# coproDeadEnd.net
KiCad netlist of a schematic drawn in EAGLE
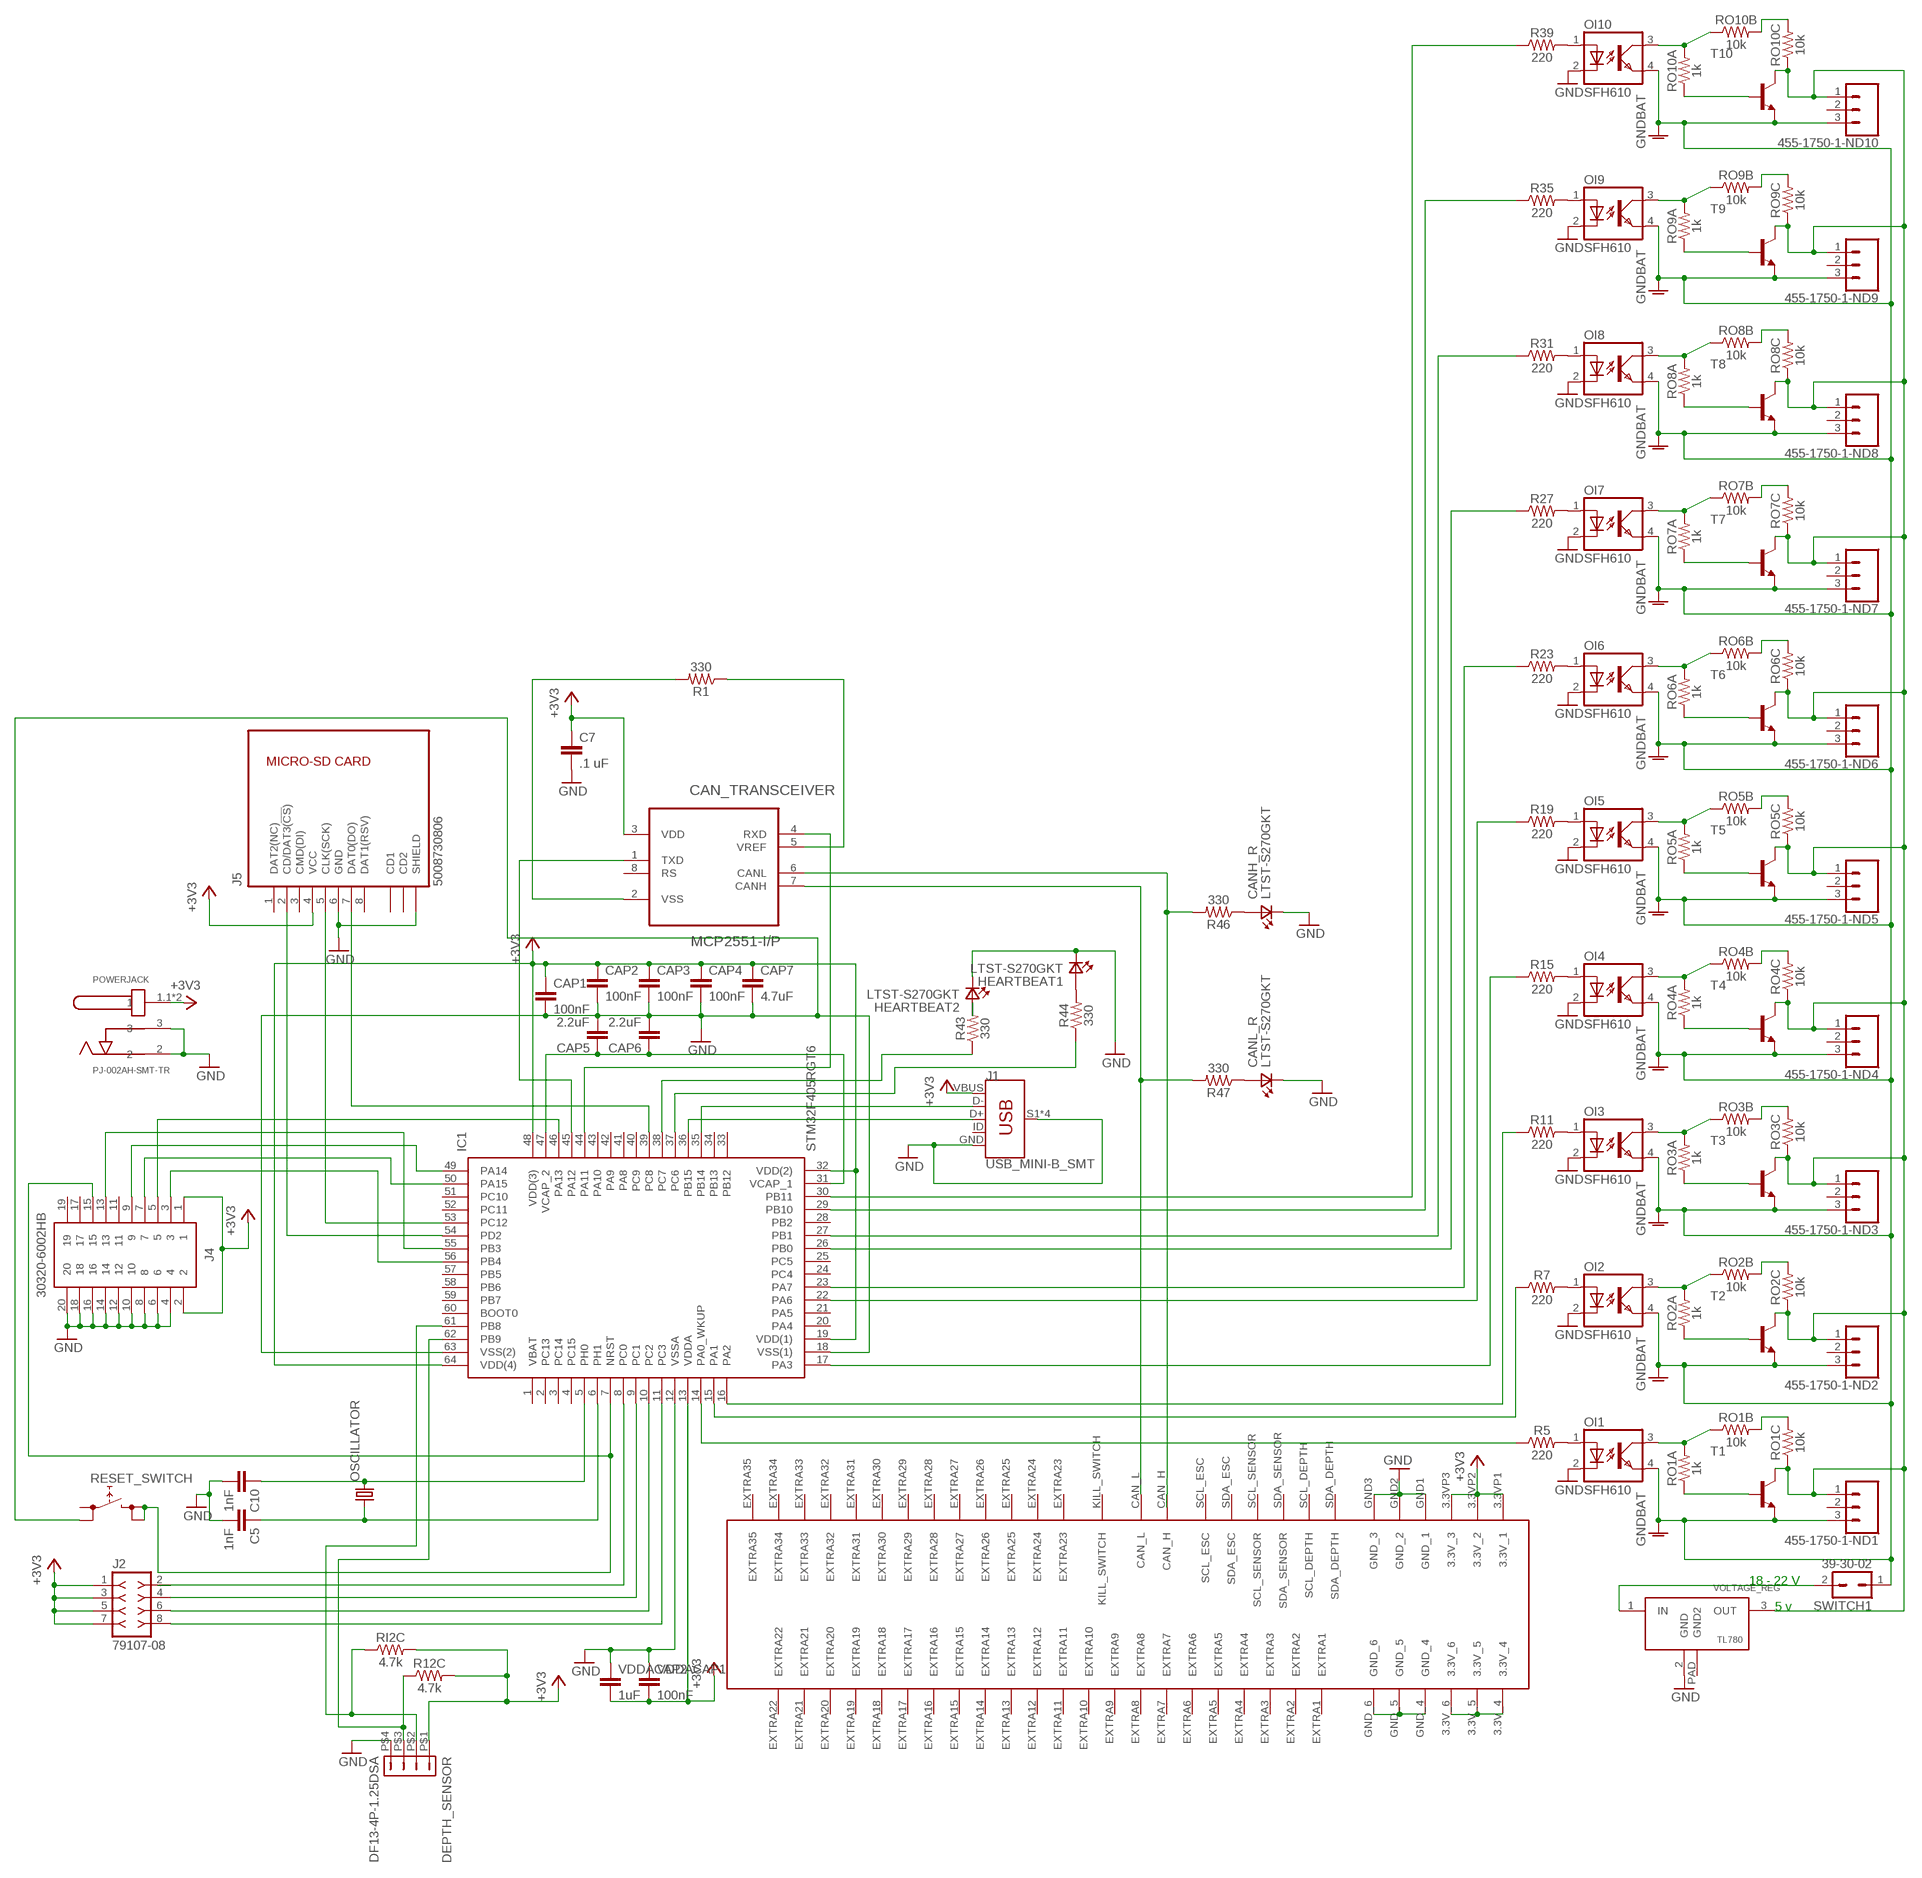
[diagram p0: schematic, sheet 1]

(export (version "E")
  (design (tool "Eeschema 10.0.6"))
  (components
    (comp (ref "455-1750-1-ND1")
      (value "CONN_03")
      (footprint "eagle-import:1X03")
      (libsource (lib "eagle-import") (part "CONN_03"))
    )
    (comp (ref "455-1750-1-ND2")
      (value "CONN_03")
      (footprint "eagle-import:1X03")
      (libsource (lib "eagle-import") (part "CONN_03"))
    )
    (comp (ref "455-1750-1-ND3")
      (value "CONN_03")
      (footprint "eagle-import:1X03")
      (libsource (lib "eagle-import") (part "CONN_03"))
    )
    (comp (ref "455-1750-1-ND4")
      (value "CONN_03")
      (footprint "eagle-import:1X03")
      (libsource (lib "eagle-import") (part "CONN_03"))
    )
    (comp (ref "455-1750-1-ND5")
      (value "CONN_03")
      (footprint "eagle-import:1X03")
      (libsource (lib "eagle-import") (part "CONN_03"))
    )
    (comp (ref "455-1750-1-ND6")
      (value "CONN_03")
      (footprint "eagle-import:1X03")
      (libsource (lib "eagle-import") (part "CONN_03"))
    )
    (comp (ref "455-1750-1-ND7")
      (value "CONN_03")
      (footprint "eagle-import:1X03")
      (libsource (lib "eagle-import") (part "CONN_03"))
    )
    (comp (ref "455-1750-1-ND8")
      (value "CONN_03")
      (footprint "eagle-import:1X03")
      (libsource (lib "eagle-import") (part "CONN_03"))
    )
    (comp (ref "455-1750-1-ND9")
      (value "CONN_03")
      (footprint "eagle-import:1X03")
      (libsource (lib "eagle-import") (part "CONN_03"))
    )
    (comp (ref "455-1750-1-ND10")
      (value "CONN_03")
      (footprint "eagle-import:1X03")
      (libsource (lib "eagle-import") (part "CONN_03"))
    )
    (comp (ref "C5")
      (value "1nF")
      (footprint "eagle-import:0603")
      (libsource (lib "eagle-import") (part "0.1UF-0603-100V-10%"))
    )
    (comp (ref "C7")
      (value ".1 uF")
      (footprint "eagle-import:0603")
      (libsource (lib "eagle-import") (part "0.1UF-0603-100V-10%"))
    )
    (comp (ref "C10")
      (value "1nF")
      (footprint "eagle-import:0603")
      (libsource (lib "eagle-import") (part "0.1UF-0603-100V-10%"))
    )
    (comp (ref "CANH_R")
      (value "LTST-S270GKT")
      (footprint "eagle-import:0603")
      (fields (field (name "MF") "Lite-On"))
      (libsource (lib "eagle-import") (part "LTST-S270GKT"))
    )
    (comp (ref "CANL_R")
      (value "LTST-S270GKT")
      (footprint "eagle-import:0603")
      (fields (field (name "MF") "Lite-On"))
      (libsource (lib "eagle-import") (part "LTST-S270GKT"))
    )
    (comp (ref "CAN_TRANSCEIVER")
      (value "MCP2551-I/P")
      (footprint "eagle-import:DIP254P762X432-8")
      (fields (field (name "DIGI-KEY_PART_NUMBER") "MCP2551-I/P-ND") (field (name "MF") "Microchip"))
      (libsource (lib "eagle-import") (part "MCP2551-I/P"))
    )
    (comp (ref "CAP1")
      (value "100nF")
      (footprint "eagle-import:0603")
      (libsource (lib "eagle-import") (part "0.1UF-0603-100V-10%"))
    )
    (comp (ref "CAP2")
      (value "100nF")
      (footprint "eagle-import:0603")
      (libsource (lib "eagle-import") (part "0.1UF-0603-100V-10%"))
    )
    (comp (ref "CAP3")
      (value "100nF")
      (footprint "eagle-import:0603")
      (libsource (lib "eagle-import") (part "0.1UF-0603-100V-10%"))
    )
    (comp (ref "CAP4")
      (value "100nF")
      (footprint "eagle-import:0603")
      (libsource (lib "eagle-import") (part "0.1UF-0603-100V-10%"))
    )
    (comp (ref "CAP5")
      (value "2.2uF")
      (footprint "eagle-import:0603")
      (libsource (lib "eagle-import") (part "0.1UF-0603-100V-10%"))
    )
    (comp (ref "CAP6")
      (value "2.2uF")
      (footprint "eagle-import:0603")
      (libsource (lib "eagle-import") (part "0.1UF-0603-100V-10%"))
    )
    (comp (ref "CAP7")
      (value "4.7uF")
      (footprint "eagle-import:0603")
      (libsource (lib "eagle-import") (part "0.1UF-0603-100V-10%"))
    )
    (comp (ref "DEPTH_SENSOR")
      (value "DF13-4P-1.25DSA")
      (footprint "eagle-import:DF13-4P-1.25DSA")
      (libsource (lib "eagle-import") (part "DF13-4P-1.25DSA"))
    )
    (comp (ref "HEARTBEAT1")
      (value "LTST-S270GKT")
      (footprint "eagle-import:0603")
      (fields (field (name "MF") "Lite-On"))
      (libsource (lib "eagle-import") (part "LTST-S270GKT"))
    )
    (comp (ref "HEARTBEAT2")
      (value "LTST-S270GKT")
      (footprint "eagle-import:0603")
      (fields (field (name "MF") "Lite-On"))
      (libsource (lib "eagle-import") (part "LTST-S270GKT"))
    )
    (comp (ref "IC1")
      (value "STM32F405RGT6")
      (footprint "eagle-import:QFP50P1200X1200X160-64N")
      (fields (field (name "RS_PART_NUMBER") "7468217"))
      (libsource (lib "eagle-import") (part "STM32F405RGT6"))
    )
    (comp (ref "J1")
      (value "USB_MINI-B_SMT")
      (footprint "eagle-import:USB-MINIB")
      (libsource (lib "eagle-import") (part "USB_MINI-B_SMT"))
    )
    (comp (ref "J2")
      (value "79107-08")
      (footprint "eagle-import:79107-08")
      (libsource (lib "eagle-import") (part "79107-08"))
    )
    (comp (ref "J4")
      (value "30320-6002HB")
      (footprint "eagle-import:SHDR20W81P254_2X10_3300X840X93")
      (fields (field (name "RS_PART_NUMBER") "8273587"))
      (libsource (lib "eagle-import") (part "30320-6002HB"))
    )
    (comp (ref "J5")
      (value "5008730806")
      (footprint "eagle-import:5008730806")
      (fields (field (name "MF") "Molex") (field (name "MP") "500873-0806"))
      (libsource (lib "eagle-import") (part "5008730806"))
    )
    (comp (ref "OI1")
      (value "SFH610")
      (footprint "eagle-import:DIL04")
      (fields (field (name "MF") "VISHAY/TELEFUNKEN") (field (name "MPN") "SFH6106-4"))
      (libsource (lib "eagle-import") (part "SFH610"))
    )
    (comp (ref "OI2")
      (value "SFH610")
      (footprint "eagle-import:DIL04")
      (fields (field (name "MF") "VISHAY/TELEFUNKEN") (field (name "MPN") "SFH6106-4"))
      (libsource (lib "eagle-import") (part "SFH610"))
    )
    (comp (ref "OI3")
      (value "SFH610")
      (footprint "eagle-import:DIL04")
      (fields (field (name "MF") "VISHAY/TELEFUNKEN") (field (name "MPN") "SFH6106-4"))
      (libsource (lib "eagle-import") (part "SFH610"))
    )
    (comp (ref "OI4")
      (value "SFH610")
      (footprint "eagle-import:DIL04")
      (fields (field (name "MF") "VISHAY/TELEFUNKEN") (field (name "MPN") "SFH6106-4"))
      (libsource (lib "eagle-import") (part "SFH610"))
    )
    (comp (ref "OI5")
      (value "SFH610")
      (footprint "eagle-import:DIL04")
      (fields (field (name "MF") "VISHAY/TELEFUNKEN") (field (name "MPN") "SFH6106-4"))
      (libsource (lib "eagle-import") (part "SFH610"))
    )
    (comp (ref "OI6")
      (value "SFH610")
      (footprint "eagle-import:DIL04")
      (fields (field (name "MF") "VISHAY/TELEFUNKEN") (field (name "MPN") "SFH6106-4"))
      (libsource (lib "eagle-import") (part "SFH610"))
    )
    (comp (ref "OI7")
      (value "SFH610")
      (footprint "eagle-import:DIL04")
      (fields (field (name "MF") "VISHAY/TELEFUNKEN") (field (name "MPN") "SFH6106-4"))
      (libsource (lib "eagle-import") (part "SFH610"))
    )
    (comp (ref "OI8")
      (value "SFH610")
      (footprint "eagle-import:DIL04")
      (fields (field (name "MF") "VISHAY/TELEFUNKEN") (field (name "MPN") "SFH6106-4"))
      (libsource (lib "eagle-import") (part "SFH610"))
    )
    (comp (ref "OI9")
      (value "SFH610")
      (footprint "eagle-import:DIL04")
      (fields (field (name "MF") "VISHAY/TELEFUNKEN") (field (name "MPN") "SFH6106-4"))
      (libsource (lib "eagle-import") (part "SFH610"))
    )
    (comp (ref "OI10")
      (value "SFH610")
      (footprint "eagle-import:DIL04")
      (fields (field (name "MF") "VISHAY/TELEFUNKEN") (field (name "MPN") "SFH6106-4"))
      (libsource (lib "eagle-import") (part "SFH610"))
    )
    (comp (ref "OSCILLATOR")
      (value "CRYSTALHC49S")
      (footprint "eagle-import:HC49_S")
      (libsource (lib "eagle-import") (part "CRYSTALHC49S"))
    )
    (comp (ref "POWERJACK")
      (value "PJ-002AH-SMT-TR")
      (footprint "eagle-import:CUI_PJ-002AH-SMT-TR")
      (fields (field (name "MF") "CUI"))
      (libsource (lib "eagle-import") (part "PJ-002AH-SMT-TR"))
    )
    (comp (ref "R1")
      (value "330")
      (footprint "eagle-import:0603")
      (libsource (lib "eagle-import") (part "1KOHM-0603-1/10W-1%"))
    )
    (comp (ref "R5")
      (value "220")
      (footprint "eagle-import:0603")
      (libsource (lib "eagle-import") (part "1KOHM-0603-1/10W-1%"))
    )
    (comp (ref "R7")
      (value "220")
      (footprint "eagle-import:0603")
      (libsource (lib "eagle-import") (part "1KOHM-0603-1/10W-1%"))
    )
    (comp (ref "R11")
      (value "220")
      (footprint "eagle-import:0603")
      (libsource (lib "eagle-import") (part "1KOHM-0603-1/10W-1%"))
    )
    (comp (ref "R12C")
      (value "4.7k")
      (footprint "eagle-import:0603")
      (libsource (lib "eagle-import") (part "1KOHM-0603-1/10W-1%"))
    )
    (comp (ref "R15")
      (value "220")
      (footprint "eagle-import:0603")
      (libsource (lib "eagle-import") (part "1KOHM-0603-1/10W-1%"))
    )
    (comp (ref "R19")
      (value "220")
      (footprint "eagle-import:0603")
      (libsource (lib "eagle-import") (part "1KOHM-0603-1/10W-1%"))
    )
    (comp (ref "R23")
      (value "220")
      (footprint "eagle-import:0603")
      (libsource (lib "eagle-import") (part "1KOHM-0603-1/10W-1%"))
    )
    (comp (ref "R27")
      (value "220")
      (footprint "eagle-import:0603")
      (libsource (lib "eagle-import") (part "1KOHM-0603-1/10W-1%"))
    )
    (comp (ref "R31")
      (value "220")
      (footprint "eagle-import:0603")
      (libsource (lib "eagle-import") (part "1KOHM-0603-1/10W-1%"))
    )
    (comp (ref "R35")
      (value "220")
      (footprint "eagle-import:0603")
      (libsource (lib "eagle-import") (part "1KOHM-0603-1/10W-1%"))
    )
    (comp (ref "R39")
      (value "220")
      (footprint "eagle-import:0603")
      (libsource (lib "eagle-import") (part "1KOHM-0603-1/10W-1%"))
    )
    (comp (ref "R43")
      (value "330")
      (footprint "eagle-import:0603")
      (libsource (lib "eagle-import") (part "1KOHM-0603-1/10W-1%"))
    )
    (comp (ref "R44")
      (value "330")
      (footprint "eagle-import:0603")
      (libsource (lib "eagle-import") (part "1KOHM-0603-1/10W-1%"))
    )
    (comp (ref "R46")
      (value "330")
      (footprint "eagle-import:0603")
      (libsource (lib "eagle-import") (part "1KOHM-0603-1/10W-1%"))
    )
    (comp (ref "R47")
      (value "330")
      (footprint "eagle-import:0603")
      (libsource (lib "eagle-import") (part "1KOHM-0603-1/10W-1%"))
    )
    (comp (ref "RESET_SWITCH")
      (value "REKN")
      (footprint "eagle-import:REKN")
      (libsource (lib "eagle-import") (part "REKN"))
    )
    (comp (ref "RI2C")
      (value "4.7k")
      (footprint "eagle-import:0603")
      (libsource (lib "eagle-import") (part "1KOHM-0603-1/10W-1%"))
    )
    (comp (ref "RO1A")
      (value "1k")
      (footprint "eagle-import:0603")
      (libsource (lib "eagle-import") (part "1KOHM-0603-1/10W-1%"))
    )
    (comp (ref "RO1B")
      (value "10k")
      (footprint "eagle-import:0603")
      (libsource (lib "eagle-import") (part "1KOHM-0603-1/10W-1%"))
    )
    (comp (ref "RO1C")
      (value "10k")
      (footprint "eagle-import:0603")
      (libsource (lib "eagle-import") (part "1KOHM-0603-1/10W-1%"))
    )
    (comp (ref "RO2A")
      (value "1k")
      (footprint "eagle-import:0603")
      (libsource (lib "eagle-import") (part "1KOHM-0603-1/10W-1%"))
    )
    (comp (ref "RO2B")
      (value "10k")
      (footprint "eagle-import:0603")
      (libsource (lib "eagle-import") (part "1KOHM-0603-1/10W-1%"))
    )
    (comp (ref "RO2C")
      (value "10k")
      (footprint "eagle-import:0603")
      (libsource (lib "eagle-import") (part "1KOHM-0603-1/10W-1%"))
    )
    (comp (ref "RO3A")
      (value "1k")
      (footprint "eagle-import:0603")
      (libsource (lib "eagle-import") (part "1KOHM-0603-1/10W-1%"))
    )
    (comp (ref "RO3B")
      (value "10k")
      (footprint "eagle-import:0603")
      (libsource (lib "eagle-import") (part "1KOHM-0603-1/10W-1%"))
    )
    (comp (ref "RO3C")
      (value "10k")
      (footprint "eagle-import:0603")
      (libsource (lib "eagle-import") (part "1KOHM-0603-1/10W-1%"))
    )
    (comp (ref "RO4A")
      (value "1k")
      (footprint "eagle-import:0603")
      (libsource (lib "eagle-import") (part "1KOHM-0603-1/10W-1%"))
    )
    (comp (ref "RO4B")
      (value "10k")
      (footprint "eagle-import:0603")
      (libsource (lib "eagle-import") (part "1KOHM-0603-1/10W-1%"))
    )
    (comp (ref "RO4C")
      (value "10k")
      (footprint "eagle-import:0603")
      (libsource (lib "eagle-import") (part "1KOHM-0603-1/10W-1%"))
    )
    (comp (ref "RO5A")
      (value "1k")
      (footprint "eagle-import:0603")
      (libsource (lib "eagle-import") (part "1KOHM-0603-1/10W-1%"))
    )
    (comp (ref "RO5B")
      (value "10k")
      (footprint "eagle-import:0603")
      (libsource (lib "eagle-import") (part "1KOHM-0603-1/10W-1%"))
    )
    (comp (ref "RO5C")
      (value "10k")
      (footprint "eagle-import:0603")
      (libsource (lib "eagle-import") (part "1KOHM-0603-1/10W-1%"))
    )
    (comp (ref "RO6A")
      (value "1k")
      (footprint "eagle-import:0603")
      (libsource (lib "eagle-import") (part "1KOHM-0603-1/10W-1%"))
    )
    (comp (ref "RO6B")
      (value "10k")
      (footprint "eagle-import:0603")
      (libsource (lib "eagle-import") (part "1KOHM-0603-1/10W-1%"))
    )
    (comp (ref "RO6C")
      (value "10k")
      (footprint "eagle-import:0603")
      (libsource (lib "eagle-import") (part "1KOHM-0603-1/10W-1%"))
    )
    (comp (ref "RO7A")
      (value "1k")
      (footprint "eagle-import:0603")
      (libsource (lib "eagle-import") (part "1KOHM-0603-1/10W-1%"))
    )
    (comp (ref "RO7B")
      (value "10k")
      (footprint "eagle-import:0603")
      (libsource (lib "eagle-import") (part "1KOHM-0603-1/10W-1%"))
    )
    (comp (ref "RO7C")
      (value "10k")
      (footprint "eagle-import:0603")
      (libsource (lib "eagle-import") (part "1KOHM-0603-1/10W-1%"))
    )
    (comp (ref "RO8A")
      (value "1k")
      (footprint "eagle-import:0603")
      (libsource (lib "eagle-import") (part "1KOHM-0603-1/10W-1%"))
    )
    (comp (ref "RO8B")
      (value "10k")
      (footprint "eagle-import:0603")
      (libsource (lib "eagle-import") (part "1KOHM-0603-1/10W-1%"))
    )
    (comp (ref "RO8C")
      (value "10k")
      (footprint "eagle-import:0603")
      (libsource (lib "eagle-import") (part "1KOHM-0603-1/10W-1%"))
    )
    (comp (ref "RO9A")
      (value "1k")
      (footprint "eagle-import:0603")
      (libsource (lib "eagle-import") (part "1KOHM-0603-1/10W-1%"))
    )
    (comp (ref "RO9B")
      (value "10k")
      (footprint "eagle-import:0603")
      (libsource (lib "eagle-import") (part "1KOHM-0603-1/10W-1%"))
    )
    (comp (ref "RO9C")
      (value "10k")
      (footprint "eagle-import:0603")
      (libsource (lib "eagle-import") (part "1KOHM-0603-1/10W-1%"))
    )
    (comp (ref "RO10A")
      (value "1k")
      (footprint "eagle-import:0603")
      (libsource (lib "eagle-import") (part "1KOHM-0603-1/10W-1%"))
    )
    (comp (ref "RO10B")
      (value "10k")
      (footprint "eagle-import:0603")
      (libsource (lib "eagle-import") (part "1KOHM-0603-1/10W-1%"))
    )
    (comp (ref "RO10C")
      (value "10k")
      (footprint "eagle-import:0603")
      (libsource (lib "eagle-import") (part "1KOHM-0603-1/10W-1%"))
    )
    (comp (ref "SWITCH1")
      (value "39-30-02")
      (footprint "eagle-import:39-30-_02_")
      (libsource (lib "eagle-import") (part "39-30-?02?"))
    )
    (comp (ref "T1")
      (value "-NPN-TO126V")
      (footprint "eagle-import:TO126V")
      (libsource (lib "eagle-import") (part "-NPN-TO126V"))
    )
    (comp (ref "T2")
      (value "-NPN-TO126V")
      (footprint "eagle-import:TO126V")
      (libsource (lib "eagle-import") (part "-NPN-TO126V"))
    )
    (comp (ref "T3")
      (value "-NPN-TO126V")
      (footprint "eagle-import:TO126V")
      (libsource (lib "eagle-import") (part "-NPN-TO126V"))
    )
    (comp (ref "T4")
      (value "-NPN-TO126V")
      (footprint "eagle-import:TO126V")
      (libsource (lib "eagle-import") (part "-NPN-TO126V"))
    )
    (comp (ref "T5")
      (value "-NPN-TO126V")
      (footprint "eagle-import:TO126V")
      (libsource (lib "eagle-import") (part "-NPN-TO126V"))
    )
    (comp (ref "T6")
      (value "-NPN-TO126V")
      (footprint "eagle-import:TO126V")
      (libsource (lib "eagle-import") (part "-NPN-TO126V"))
    )
    (comp (ref "T7")
      (value "-NPN-TO126V")
      (footprint "eagle-import:TO126V")
      (libsource (lib "eagle-import") (part "-NPN-TO126V"))
    )
    (comp (ref "T8")
      (value "-NPN-TO126V")
      (footprint "eagle-import:TO126V")
      (libsource (lib "eagle-import") (part "-NPN-TO126V"))
    )
    (comp (ref "T9")
      (value "-NPN-TO126V")
      (footprint "eagle-import:TO126V")
      (libsource (lib "eagle-import") (part "-NPN-TO126V"))
    )
    (comp (ref "T10")
      (value "-NPN-TO126V")
      (footprint "eagle-import:TO126V")
      (libsource (lib "eagle-import") (part "-NPN-TO126V"))
    )
    (comp (ref "U$1")
      (value "5530843")
      (footprint "eagle-import:5530843-6-BOARDFINGERS")
      (libsource (lib "eagle-import") (part "5530843"))
    )
    (comp (ref "VDDACAP1")
      (value "100nF")
      (footprint "eagle-import:0603")
      (libsource (lib "eagle-import") (part "0.1UF-0603-100V-10%"))
    )
    (comp (ref "VDDACAP2")
      (value "1uF")
      (footprint "eagle-import:0603")
      (libsource (lib "eagle-import") (part "0.1UF-0603-100V-10%"))
    )
    (comp (ref "VOLTAGE_REG")
      (value "TL780_VREG")
      (footprint "eagle-import:D2PAK-3")
      (fields (field (name "MF") "Texas Instruments") (field (name "MP") "TL780-05KCSE3"))
      (libsource (lib "eagle-import") (part "TL780_VREG"))
    )
  )
  (nets
    (net (code "1") (name "+3V3") (class "Default")
      (node (ref "C7") (pin "1") (pinfunction "1_1") (pintype "passive"))
      (node (ref "CAN_TRANSCEIVER") (pin "3") (pinfunction "VDD_3") (pintype "power_in"))
      (node (ref "CAP1") (pin "1") (pinfunction "1_1") (pintype "passive"))
      (node (ref "CAP2") (pin "1") (pinfunction "1_1") (pintype "passive"))
      (node (ref "CAP3") (pin "1") (pinfunction "1_1") (pintype "passive"))
      (node (ref "CAP4") (pin "1") (pinfunction "1_1") (pintype "passive"))
      (node (ref "CAP7") (pin "1") (pinfunction "1_1") (pintype "passive"))
      (node (ref "DEPTH_SENSOR") (pin "P$1") (pinfunction "1_P$1") (pintype "passive"))
      (node (ref "IC1") (pin "13") (pinfunction "VDDA_13") (pintype "power_in"))
      (node (ref "IC1") (pin "19") (pinfunction "VDD(1)_19") (pintype "power_in"))
      (node (ref "IC1") (pin "32") (pinfunction "VDD(2)_32") (pintype "power_in"))
      (node (ref "IC1") (pin "48") (pinfunction "VDD(3)_48") (pintype "power_in"))
      (node (ref "IC1") (pin "64") (pinfunction "VDD(4)_64") (pintype "power_in"))
      (node (ref "J1") (pin "VBUS") (pinfunction "VBUS_VBUS") (pintype "power_in"))
      (node (ref "J2") (pin "1") (pinfunction "1_1") (pintype "passive"))
      (node (ref "J2") (pin "3") (pinfunction "3_3") (pintype "passive"))
      (node (ref "J2") (pin "5") (pinfunction "5_5") (pintype "passive"))
      (node (ref "J2") (pin "7") (pinfunction "7_7") (pintype "passive"))
      (node (ref "J4") (pin "1") (pinfunction "1_1") (pintype "passive"))
      (node (ref "J4") (pin "2") (pinfunction "2_2") (pintype "passive"))
      (node (ref "J5") (pin "4") (pinfunction "VCC_4") (pintype "bidirectional"))
      (node (ref "POWERJACK") (pin "1.1") (pinfunction "1_1.1") (pintype "passive"))
      (node (ref "POWERJACK") (pin "1.2") (pinfunction "1_1.2") (pintype "passive"))
      (node (ref "R12C") (pin "2") (pinfunction "2_2") (pintype "passive"))
      (node (ref "RI2C") (pin "2") (pinfunction "2_2") (pintype "passive"))
      (node (ref "U$1") (pin "3.3VP1") (pinfunction "3.3V_1_3.3VP1") (pintype "bidirectional"))
      (node (ref "U$1") (pin "3.3VP2") (pinfunction "3.3V_2_3.3VP2") (pintype "bidirectional"))
      (node (ref "U$1") (pin "3.3VP3") (pinfunction "3.3V_3_3.3VP3") (pintype "bidirectional"))
      (node (ref "VDDACAP1") (pin "2") (pinfunction "2_2") (pintype "passive"))
      (node (ref "VDDACAP2") (pin "2") (pinfunction "2_2") (pintype "passive"))
    )
    (net (code "2") (name "GND") (class "Default")
      (node (ref "C10") (pin "2") (pinfunction "2_2") (pintype "passive"))
      (node (ref "C5") (pin "2") (pinfunction "2_2") (pintype "passive"))
      (node (ref "C7") (pin "2") (pinfunction "2_2") (pintype "passive"))
      (node (ref "CANH_R") (pin "1") (pinfunction "K2_1") (pintype "passive"))
      (node (ref "CANL_R") (pin "1") (pinfunction "K2_1") (pintype "passive"))
      (node (ref "CAP1") (pin "2") (pinfunction "2_2") (pintype "passive"))
      (node (ref "CAP2") (pin "2") (pinfunction "2_2") (pintype "passive"))
      (node (ref "CAP3") (pin "2") (pinfunction "2_2") (pintype "passive"))
      (node (ref "CAP4") (pin "2") (pinfunction "2_2") (pintype "passive"))
      (node (ref "CAP5") (pin "2") (pinfunction "2_2") (pintype "passive"))
      (node (ref "CAP6") (pin "2") (pinfunction "2_2") (pintype "passive"))
      (node (ref "CAP7") (pin "2") (pinfunction "2_2") (pintype "passive"))
      (node (ref "DEPTH_SENSOR") (pin "P$4") (pinfunction "4_P$4") (pintype "passive"))
      (node (ref "HEARTBEAT1") (pin "1") (pinfunction "K2_1") (pintype "passive"))
      (node (ref "HEARTBEAT2") (pin "1") (pinfunction "K2_1") (pintype "passive"))
      (node (ref "IC1") (pin "12") (pinfunction "VSSA_12") (pintype "power_in"))
      (node (ref "IC1") (pin "18") (pinfunction "VSS(1)_18") (pintype "power_in"))
      (node (ref "IC1") (pin "63") (pinfunction "VSS(2)_63") (pintype "power_in"))
      (node (ref "J1") (pin "GND") (pinfunction "GND_GND") (pintype "power_in"))
      (node (ref "J1") (pin "S1") (pinfunction "SHIELD_S1") (pintype "bidirectional"))
      (node (ref "J1") (pin "S2") (pinfunction "SHIELD_S2") (pintype "bidirectional"))
      (node (ref "J1") (pin "S3") (pinfunction "SHIELD_S3") (pintype "bidirectional"))
      (node (ref "J1") (pin "S4") (pinfunction "SHIELD_S4") (pintype "bidirectional"))
      (node (ref "J4") (pin "10") (pinfunction "10_10") (pintype "passive"))
      (node (ref "J4") (pin "12") (pinfunction "12_12") (pintype "passive"))
      (node (ref "J4") (pin "14") (pinfunction "14_14") (pintype "passive"))
      (node (ref "J4") (pin "16") (pinfunction "16_16") (pintype "passive"))
      (node (ref "J4") (pin "18") (pinfunction "18_18") (pintype "passive"))
      (node (ref "J4") (pin "20") (pinfunction "20_20") (pintype "passive"))
      (node (ref "J4") (pin "4") (pinfunction "4_4") (pintype "passive"))
      (node (ref "J4") (pin "6") (pinfunction "6_6") (pintype "passive"))
      (node (ref "J4") (pin "8") (pinfunction "8_8") (pintype "passive"))
      (node (ref "J5") (pin "6") (pinfunction "GND_6") (pintype "bidirectional"))
      (node (ref "J5") (pin "S3") (pinfunction "SHIELD_S3") (pintype "bidirectional"))
      (node (ref "J5") (pin "S4") (pinfunction "SHIELD_S4") (pintype "bidirectional"))
      (node (ref "OI1") (pin "2") (pinfunction "C_2") (pintype "passive"))
      (node (ref "OI10") (pin "2") (pinfunction "C_2") (pintype "passive"))
      (node (ref "OI2") (pin "2") (pinfunction "C_2") (pintype "passive"))
      (node (ref "OI3") (pin "2") (pinfunction "C_2") (pintype "passive"))
      (node (ref "OI4") (pin "2") (pinfunction "C_2") (pintype "passive"))
      (node (ref "OI5") (pin "2") (pinfunction "C_2") (pintype "passive"))
      (node (ref "OI6") (pin "2") (pinfunction "C_2") (pintype "passive"))
      (node (ref "OI7") (pin "2") (pinfunction "C_2") (pintype "passive"))
      (node (ref "OI8") (pin "2") (pinfunction "C_2") (pintype "passive"))
      (node (ref "OI9") (pin "2") (pinfunction "C_2") (pintype "passive"))
      (node (ref "POWERJACK") (pin "2") (pinfunction "2_2") (pintype "passive"))
      (node (ref "POWERJACK") (pin "3") (pinfunction "3_3") (pintype "passive"))
      (node (ref "RESET_SWITCH") (pin "0B") (pinfunction "0_0B") (pintype "passive"))
      (node (ref "U$1") (pin "GND1") (pinfunction "GND_1_GND1") (pintype "bidirectional"))
      (node (ref "U$1") (pin "GND2") (pinfunction "GND_2_GND2") (pintype "bidirectional"))
      (node (ref "U$1") (pin "GND3") (pinfunction "GND_3_GND3") (pintype "bidirectional"))
      (node (ref "U$1") (pin "GND_4") (pinfunction "GND_4_GND_4") (pintype "bidirectional"))
      (node (ref "U$1") (pin "GND_5") (pinfunction "GND_5_GND_5") (pintype "bidirectional"))
      (node (ref "U$1") (pin "GND_6") (pinfunction "GND_6_GND_6") (pintype "bidirectional"))
      (node (ref "VDDACAP1") (pin "1") (pinfunction "1_1") (pintype "passive"))
      (node (ref "VDDACAP2") (pin "1") (pinfunction "1_1") (pintype "passive"))
      (node (ref "VOLTAGE_REG") (pin "2") (pinfunction "GND_2") (pintype "bidirectional"))
    )
    (net (code "3") (name "GNDBAT") (class "Default")
      (node (ref "455-1750-1-ND1") (pin "3") (pinfunction "3_3") (pintype "passive"))
      (node (ref "455-1750-1-ND10") (pin "3") (pinfunction "3_3") (pintype "passive"))
      (node (ref "455-1750-1-ND2") (pin "3") (pinfunction "3_3") (pintype "passive"))
      (node (ref "455-1750-1-ND3") (pin "3") (pinfunction "3_3") (pintype "passive"))
      (node (ref "455-1750-1-ND4") (pin "3") (pinfunction "3_3") (pintype "passive"))
      (node (ref "455-1750-1-ND5") (pin "3") (pinfunction "3_3") (pintype "passive"))
      (node (ref "455-1750-1-ND6") (pin "3") (pinfunction "3_3") (pintype "passive"))
      (node (ref "455-1750-1-ND7") (pin "3") (pinfunction "3_3") (pintype "passive"))
      (node (ref "455-1750-1-ND8") (pin "3") (pinfunction "3_3") (pintype "passive"))
      (node (ref "455-1750-1-ND9") (pin "3") (pinfunction "3_3") (pintype "passive"))
      (node (ref "OI1") (pin "4") (pinfunction "EMIT_4") (pintype "passive"))
      (node (ref "OI10") (pin "4") (pinfunction "EMIT_4") (pintype "passive"))
      (node (ref "OI2") (pin "4") (pinfunction "EMIT_4") (pintype "passive"))
      (node (ref "OI3") (pin "4") (pinfunction "EMIT_4") (pintype "passive"))
      (node (ref "OI4") (pin "4") (pinfunction "EMIT_4") (pintype "passive"))
      (node (ref "OI5") (pin "4") (pinfunction "EMIT_4") (pintype "passive"))
      (node (ref "OI6") (pin "4") (pinfunction "EMIT_4") (pintype "passive"))
      (node (ref "OI7") (pin "4") (pinfunction "EMIT_4") (pintype "passive"))
      (node (ref "OI8") (pin "4") (pinfunction "EMIT_4") (pintype "passive"))
      (node (ref "OI9") (pin "4") (pinfunction "EMIT_4") (pintype "passive"))
      (node (ref "SWITCH1") (pin "1") (pinfunction "1_1") (pintype "passive"))
      (node (ref "T1") (pin "1") (pinfunction "E_1") (pintype "passive"))
      (node (ref "T10") (pin "1") (pinfunction "E_1") (pintype "passive"))
      (node (ref "T2") (pin "1") (pinfunction "E_1") (pintype "passive"))
      (node (ref "T3") (pin "1") (pinfunction "E_1") (pintype "passive"))
      (node (ref "T4") (pin "1") (pinfunction "E_1") (pintype "passive"))
      (node (ref "T5") (pin "1") (pinfunction "E_1") (pintype "passive"))
      (node (ref "T6") (pin "1") (pinfunction "E_1") (pintype "passive"))
      (node (ref "T7") (pin "1") (pinfunction "E_1") (pintype "passive"))
      (node (ref "T8") (pin "1") (pinfunction "E_1") (pintype "passive"))
      (node (ref "T9") (pin "1") (pinfunction "E_1") (pintype "passive"))
    )
    (net (code "4") (name "Net-(CANH_R-A2)") (class "Default")
      (node (ref "CANH_R") (pin "2") (pinfunction "A2_2") (pintype "passive"))
      (node (ref "R46") (pin "1") (pinfunction "1_1") (pintype "passive"))
    )
    (net (code "5") (name "Net-(CANL_R-A2)") (class "Default")
      (node (ref "CANL_R") (pin "2") (pinfunction "A2_2") (pintype "passive"))
      (node (ref "R47") (pin "1") (pinfunction "1_1") (pintype "passive"))
    )
    (net (code "6") (name "Net-(CAN_TRANSCEIVER-CANH)") (class "Default")
      (node (ref "CAN_TRANSCEIVER") (pin "7") (pinfunction "CANH_7") (pintype "bidirectional"))
      (node (ref "R47") (pin "2") (pinfunction "2_2") (pintype "passive"))
      (node (ref "U$1") (pin "CAN_L") (pinfunction "CAN_L_CAN_L") (pintype "bidirectional"))
    )
    (net (code "7") (name "Net-(CAN_TRANSCEIVER-CANL)") (class "Default")
      (node (ref "CAN_TRANSCEIVER") (pin "6") (pinfunction "CANL_6") (pintype "bidirectional"))
      (node (ref "R46") (pin "2") (pinfunction "2_2") (pintype "passive"))
      (node (ref "U$1") (pin "CAN_H") (pinfunction "CAN_H_CAN_H") (pintype "bidirectional"))
    )
    (net (code "8") (name "Net-(CAN_TRANSCEIVER-RXD)") (class "Default")
      (node (ref "CAN_TRANSCEIVER") (pin "4") (pinfunction "RXD_4") (pintype "output"))
      (node (ref "IC1") (pin "44") (pinfunction "PA11_44") (pintype "passive"))
    )
    (net (code "9") (name "Net-(CAN_TRANSCEIVER-TXD)") (class "Default")
      (node (ref "CAN_TRANSCEIVER") (pin "1") (pinfunction "TXD_1") (pintype "input"))
      (node (ref "IC1") (pin "45") (pinfunction "PA12_45") (pintype "passive"))
    )
    (net (code "10") (name "Net-(CAN_TRANSCEIVER-VREF)") (class "Default")
      (node (ref "CAN_TRANSCEIVER") (pin "5") (pinfunction "VREF_5") (pintype "output"))
      (node (ref "R1") (pin "1") (pinfunction "1_1") (pintype "passive"))
    )
    (net (code "11") (name "Net-(CAN_TRANSCEIVER-VSS)") (class "Default")
      (node (ref "CAN_TRANSCEIVER") (pin "2") (pinfunction "VSS_2") (pintype "power_in"))
      (node (ref "R1") (pin "2") (pinfunction "2_2") (pintype "passive"))
    )
    (net (code "12") (name "Net-(DEPTH_SENSOR-2)") (class "Default")
      (node (ref "DEPTH_SENSOR") (pin "P$2") (pinfunction "2_P$2") (pintype "passive"))
      (node (ref "IC1") (pin "61") (pinfunction "PB8_61") (pintype "passive"))
      (node (ref "RI2C") (pin "1") (pinfunction "1_1") (pintype "passive"))
    )
    (net (code "13") (name "Net-(DEPTH_SENSOR-3)") (class "Default")
      (node (ref "DEPTH_SENSOR") (pin "P$3") (pinfunction "3_P$3") (pintype "passive"))
      (node (ref "IC1") (pin "62") (pinfunction "PB9_62") (pintype "passive"))
      (node (ref "R12C") (pin "1") (pinfunction "1_1") (pintype "passive"))
    )
    (net (code "14") (name "Net-(HEARTBEAT1-A2)") (class "Default")
      (node (ref "HEARTBEAT1") (pin "2") (pinfunction "A2_2") (pintype "passive"))
      (node (ref "R44") (pin "2") (pinfunction "2_2") (pintype "passive"))
    )
    (net (code "15") (name "Net-(HEARTBEAT2-A2)") (class "Default")
      (node (ref "HEARTBEAT2") (pin "2") (pinfunction "A2_2") (pintype "passive"))
      (node (ref "R43") (pin "2") (pinfunction "2_2") (pintype "passive"))
    )
    (net (code "16") (name "Net-(IC1-NRST)") (class "Default")
      (node (ref "IC1") (pin "7") (pinfunction "NRST_7") (pintype "input"))
      (node (ref "J4") (pin "15") (pinfunction "15_15") (pintype "passive"))
      (node (ref "RESET_SWITCH") (pin "1A") (pinfunction "1_1A") (pintype "passive"))
      (node (ref "RESET_SWITCH") (pin "1B") (pinfunction "1_1B") (pintype "passive"))
    )
    (net (code "17") (name "Net-(IC1-PA0_WKUP)") (class "Default")
      (node (ref "IC1") (pin "14") (pinfunction "PA0_WKUP_14") (pintype "passive"))
      (node (ref "R5") (pin "1") (pinfunction "1_1") (pintype "passive"))
    )
    (net (code "18") (name "Net-(IC1-PA1)") (class "Default")
      (node (ref "IC1") (pin "15") (pinfunction "PA1_15") (pintype "passive"))
      (node (ref "R7") (pin "1") (pinfunction "1_1") (pintype "passive"))
    )
    (net (code "19") (name "Net-(IC1-PA2)") (class "Default")
      (node (ref "IC1") (pin "16") (pinfunction "PA2_16") (pintype "passive"))
      (node (ref "R11") (pin "1") (pinfunction "1_1") (pintype "passive"))
    )
    (net (code "20") (name "Net-(IC1-PA3)") (class "Default")
      (node (ref "IC1") (pin "17") (pinfunction "PA3_17") (pintype "passive"))
      (node (ref "R15") (pin "1") (pinfunction "1_1") (pintype "passive"))
    )
    (net (code "21") (name "Net-(IC1-PA6)") (class "Default")
      (node (ref "IC1") (pin "22") (pinfunction "PA6_22") (pintype "passive"))
      (node (ref "R19") (pin "1") (pinfunction "1_1") (pintype "passive"))
    )
    (net (code "22") (name "Net-(IC1-PA7)") (class "Default")
      (node (ref "IC1") (pin "23") (pinfunction "PA7_23") (pintype "passive"))
      (node (ref "R23") (pin "1") (pinfunction "1_1") (pintype "passive"))
    )
    (net (code "23") (name "Net-(IC1-PA13)") (class "Default")
      (node (ref "IC1") (pin "46") (pinfunction "PA13_46") (pintype "passive"))
      (node (ref "J4") (pin "5") (pinfunction "5_5") (pintype "passive"))
    )
    (net (code "24") (name "Net-(IC1-PA14)") (class "Default")
      (node (ref "IC1") (pin "49") (pinfunction "PA14_49") (pintype "passive"))
      (node (ref "J4") (pin "9") (pinfunction "9_9") (pintype "passive"))
    )
    (net (code "25") (name "Net-(IC1-PA15)") (class "Default")
      (node (ref "IC1") (pin "50") (pinfunction "PA15_50") (pintype "passive"))
      (node (ref "J4") (pin "7") (pinfunction "7_7") (pintype "passive"))
    )
    (net (code "26") (name "Net-(IC1-PB0)") (class "Default")
      (node (ref "IC1") (pin "26") (pinfunction "PB0_26") (pintype "passive"))
      (node (ref "R27") (pin "1") (pinfunction "1_1") (pintype "passive"))
    )
    (net (code "27") (name "Net-(IC1-PB1)") (class "Default")
      (node (ref "IC1") (pin "27") (pinfunction "PB1_27") (pintype "passive"))
      (node (ref "R31") (pin "1") (pinfunction "1_1") (pintype "passive"))
    )
    (net (code "28") (name "Net-(IC1-PB3)") (class "Default")
      (node (ref "IC1") (pin "55") (pinfunction "PB3_55") (pintype "passive"))
      (node (ref "J4") (pin "13") (pinfunction "13_13") (pintype "passive"))
    )
    (net (code "29") (name "Net-(IC1-PB4)") (class "Default")
      (node (ref "IC1") (pin "56") (pinfunction "PB4_56") (pintype "passive"))
      (node (ref "J4") (pin "3") (pinfunction "3_3") (pintype "passive"))
    )
    (net (code "30") (name "Net-(IC1-PB10)") (class "Default")
      (node (ref "IC1") (pin "29") (pinfunction "PB10_29") (pintype "passive"))
      (node (ref "R35") (pin "1") (pinfunction "1_1") (pintype "passive"))
    )
    (net (code "31") (name "Net-(IC1-PB11)") (class "Default")
      (node (ref "IC1") (pin "30") (pinfunction "PB11_30") (pintype "passive"))
      (node (ref "R39") (pin "1") (pinfunction "1_1") (pintype "passive"))
    )
    (net (code "32") (name "Net-(IC1-PB14)") (class "Default")
      (node (ref "IC1") (pin "35") (pinfunction "PB14_35") (pintype "passive"))
      (node (ref "J1") (pin "D-") (pinfunction "D-_D-") (pintype "bidirectional"))
    )
    (net (code "33") (name "Net-(IC1-PB15)") (class "Default")
      (node (ref "IC1") (pin "36") (pinfunction "PB15_36") (pintype "passive"))
      (node (ref "J1") (pin "D+") (pinfunction "D+_D+") (pintype "bidirectional"))
    )
    (net (code "34") (name "Net-(IC1-PC0)") (class "Default")
      (node (ref "IC1") (pin "8") (pinfunction "PC0_8") (pintype "passive"))
      (node (ref "J2") (pin "2") (pinfunction "2_2") (pintype "passive"))
    )
    (net (code "35") (name "Net-(IC1-PC1)") (class "Default")
      (node (ref "IC1") (pin "9") (pinfunction "PC1_9") (pintype "passive"))
      (node (ref "J2") (pin "4") (pinfunction "4_4") (pintype "passive"))
    )
    (net (code "36") (name "Net-(IC1-PC2)") (class "Default")
      (node (ref "IC1") (pin "10") (pinfunction "PC2_10") (pintype "passive"))
      (node (ref "J2") (pin "6") (pinfunction "6_6") (pintype "passive"))
    )
    (net (code "37") (name "Net-(IC1-PC3)") (class "Default")
      (node (ref "IC1") (pin "11") (pinfunction "PC3_11") (pintype "passive"))
      (node (ref "J2") (pin "8") (pinfunction "8_8") (pintype "passive"))
    )
    (net (code "38") (name "Net-(IC1-PC6)") (class "Default")
      (node (ref "IC1") (pin "37") (pinfunction "PC6_37") (pintype "passive"))
      (node (ref "R44") (pin "1") (pinfunction "1_1") (pintype "passive"))
    )
    (net (code "39") (name "Net-(IC1-PC7)") (class "Default")
      (node (ref "IC1") (pin "38") (pinfunction "PC7_38") (pintype "passive"))
      (node (ref "R43") (pin "1") (pinfunction "1_1") (pintype "passive"))
    )
    (net (code "40") (name "Net-(IC1-PC8)") (class "Default")
      (node (ref "IC1") (pin "39") (pinfunction "PC8_39") (pintype "passive"))
      (node (ref "J5") (pin "7") (pinfunction "DAT0(DO)_7") (pintype "bidirectional"))
    )
    (net (code "41") (name "Net-(IC1-PC12)") (class "Default")
      (node (ref "IC1") (pin "53") (pinfunction "PC12_53") (pintype "passive"))
      (node (ref "J5") (pin "5") (pinfunction "CLK(SCK)_5") (pintype "bidirectional"))
    )
    (net (code "42") (name "Net-(IC1-PD2)") (class "Default")
      (node (ref "IC1") (pin "54") (pinfunction "PD2_54") (pintype "passive"))
      (node (ref "J5") (pin "2") (pinfunction "CD/DAT3(~{CS})_2") (pintype "bidirectional"))
    )
    (net (code "43") (name "Net-(IC1-PH0)") (class "Default")
      (node (ref "C10") (pin "1") (pinfunction "1_1") (pintype "passive"))
      (node (ref "IC1") (pin "5") (pinfunction "PH0_5") (pintype "passive"))
      (node (ref "OSCILLATOR") (pin "2") (pinfunction "2_2") (pintype "passive"))
    )
    (net (code "44") (name "Net-(IC1-PH1)") (class "Default")
      (node (ref "C5") (pin "1") (pinfunction "1_1") (pintype "passive"))
      (node (ref "IC1") (pin "6") (pinfunction "PH1_6") (pintype "passive"))
      (node (ref "OSCILLATOR") (pin "1") (pinfunction "1_1") (pintype "passive"))
    )
    (net (code "45") (name "Net-(IC1-VCAP_1)") (class "Default")
      (node (ref "CAP5") (pin "1") (pinfunction "1_1") (pintype "passive"))
      (node (ref "CAP6") (pin "1") (pinfunction "1_1") (pintype "passive"))
      (node (ref "IC1") (pin "31") (pinfunction "VCAP_1_31") (pintype "passive"))
      (node (ref "IC1") (pin "47") (pinfunction "VCAP_2_47") (pintype "passive"))
    )
    (net (code "46") (name "Net-(OI1-A)") (class "Default")
      (node (ref "OI1") (pin "1") (pinfunction "A_1") (pintype "passive"))
      (node (ref "R5") (pin "2") (pinfunction "2_2") (pintype "passive"))
    )
    (net (code "47") (name "Net-(OI1-COL)") (class "Default")
      (node (ref "OI1") (pin "3") (pinfunction "COL_3") (pintype "passive"))
      (node (ref "RO1A") (pin "2") (pinfunction "2_2") (pintype "passive"))
      (node (ref "RO1B") (pin "1") (pinfunction "1_1") (pintype "passive"))
    )
    (net (code "48") (name "Net-(OI2-A)") (class "Default")
      (node (ref "OI2") (pin "1") (pinfunction "A_1") (pintype "passive"))
      (node (ref "R7") (pin "2") (pinfunction "2_2") (pintype "passive"))
    )
    (net (code "49") (name "Net-(OI2-COL)") (class "Default")
      (node (ref "OI2") (pin "3") (pinfunction "COL_3") (pintype "passive"))
      (node (ref "RO2A") (pin "2") (pinfunction "2_2") (pintype "passive"))
      (node (ref "RO2B") (pin "1") (pinfunction "1_1") (pintype "passive"))
    )
    (net (code "50") (name "Net-(OI3-A)") (class "Default")
      (node (ref "OI3") (pin "1") (pinfunction "A_1") (pintype "passive"))
      (node (ref "R11") (pin "2") (pinfunction "2_2") (pintype "passive"))
    )
    (net (code "51") (name "Net-(OI3-COL)") (class "Default")
      (node (ref "OI3") (pin "3") (pinfunction "COL_3") (pintype "passive"))
      (node (ref "RO3A") (pin "2") (pinfunction "2_2") (pintype "passive"))
      (node (ref "RO3B") (pin "1") (pinfunction "1_1") (pintype "passive"))
    )
    (net (code "52") (name "Net-(OI4-A)") (class "Default")
      (node (ref "OI4") (pin "1") (pinfunction "A_1") (pintype "passive"))
      (node (ref "R15") (pin "2") (pinfunction "2_2") (pintype "passive"))
    )
    (net (code "53") (name "Net-(OI4-COL)") (class "Default")
      (node (ref "OI4") (pin "3") (pinfunction "COL_3") (pintype "passive"))
      (node (ref "RO4A") (pin "2") (pinfunction "2_2") (pintype "passive"))
      (node (ref "RO4B") (pin "1") (pinfunction "1_1") (pintype "passive"))
    )
    (net (code "54") (name "Net-(OI5-A)") (class "Default")
      (node (ref "OI5") (pin "1") (pinfunction "A_1") (pintype "passive"))
      (node (ref "R19") (pin "2") (pinfunction "2_2") (pintype "passive"))
    )
    (net (code "55") (name "Net-(OI5-COL)") (class "Default")
      (node (ref "OI5") (pin "3") (pinfunction "COL_3") (pintype "passive"))
      (node (ref "RO5A") (pin "2") (pinfunction "2_2") (pintype "passive"))
      (node (ref "RO5B") (pin "1") (pinfunction "1_1") (pintype "passive"))
    )
    (net (code "56") (name "Net-(OI6-A)") (class "Default")
      (node (ref "OI6") (pin "1") (pinfunction "A_1") (pintype "passive"))
      (node (ref "R23") (pin "2") (pinfunction "2_2") (pintype "passive"))
    )
    (net (code "57") (name "Net-(OI6-COL)") (class "Default")
      (node (ref "OI6") (pin "3") (pinfunction "COL_3") (pintype "passive"))
      (node (ref "RO6A") (pin "2") (pinfunction "2_2") (pintype "passive"))
      (node (ref "RO6B") (pin "1") (pinfunction "1_1") (pintype "passive"))
    )
    (net (code "58") (name "Net-(OI7-A)") (class "Default")
      (node (ref "OI7") (pin "1") (pinfunction "A_1") (pintype "passive"))
      (node (ref "R27") (pin "2") (pinfunction "2_2") (pintype "passive"))
    )
    (net (code "59") (name "Net-(OI7-COL)") (class "Default")
      (node (ref "OI7") (pin "3") (pinfunction "COL_3") (pintype "passive"))
      (node (ref "RO7A") (pin "2") (pinfunction "2_2") (pintype "passive"))
      (node (ref "RO7B") (pin "1") (pinfunction "1_1") (pintype "passive"))
    )
    (net (code "60") (name "Net-(OI8-A)") (class "Default")
      (node (ref "OI8") (pin "1") (pinfunction "A_1") (pintype "passive"))
      (node (ref "R31") (pin "2") (pinfunction "2_2") (pintype "passive"))
    )
    (net (code "61") (name "Net-(OI8-COL)") (class "Default")
      (node (ref "OI8") (pin "3") (pinfunction "COL_3") (pintype "passive"))
      (node (ref "RO8A") (pin "2") (pinfunction "2_2") (pintype "passive"))
      (node (ref "RO8B") (pin "1") (pinfunction "1_1") (pintype "passive"))
    )
    (net (code "62") (name "Net-(OI9-A)") (class "Default")
      (node (ref "OI9") (pin "1") (pinfunction "A_1") (pintype "passive"))
      (node (ref "R35") (pin "2") (pinfunction "2_2") (pintype "passive"))
    )
    (net (code "63") (name "Net-(OI9-COL)") (class "Default")
      (node (ref "OI9") (pin "3") (pinfunction "COL_3") (pintype "passive"))
      (node (ref "RO9A") (pin "2") (pinfunction "2_2") (pintype "passive"))
      (node (ref "RO9B") (pin "1") (pinfunction "1_1") (pintype "passive"))
    )
    (net (code "64") (name "Net-(OI10-A)") (class "Default")
      (node (ref "OI10") (pin "1") (pinfunction "A_1") (pintype "passive"))
      (node (ref "R39") (pin "2") (pinfunction "2_2") (pintype "passive"))
    )
    (net (code "65") (name "Net-(OI10-COL)") (class "Default")
      (node (ref "OI10") (pin "3") (pinfunction "COL_3") (pintype "passive"))
      (node (ref "RO10A") (pin "2") (pinfunction "2_2") (pintype "passive"))
      (node (ref "RO10B") (pin "1") (pinfunction "1_1") (pintype "passive"))
    )
    (net (code "66") (name "Net-(RO1B-Pad2)") (class "Default")
      (node (ref "RO1B") (pin "2") (pinfunction "2_2") (pintype "passive"))
      (node (ref "RO1C") (pin "2") (pinfunction "2_2") (pintype "passive"))
    )
    (net (code "67") (name "Net-(RO2B-Pad2)") (class "Default")
      (node (ref "RO2B") (pin "2") (pinfunction "2_2") (pintype "passive"))
      (node (ref "RO2C") (pin "2") (pinfunction "2_2") (pintype "passive"))
    )
    (net (code "68") (name "Net-(RO3B-Pad2)") (class "Default")
      (node (ref "RO3B") (pin "2") (pinfunction "2_2") (pintype "passive"))
      (node (ref "RO3C") (pin "2") (pinfunction "2_2") (pintype "passive"))
    )
    (net (code "69") (name "Net-(RO4B-Pad2)") (class "Default")
      (node (ref "RO4B") (pin "2") (pinfunction "2_2") (pintype "passive"))
      (node (ref "RO4C") (pin "2") (pinfunction "2_2") (pintype "passive"))
    )
    (net (code "70") (name "Net-(RO5B-Pad2)") (class "Default")
      (node (ref "RO5B") (pin "2") (pinfunction "2_2") (pintype "passive"))
      (node (ref "RO5C") (pin "2") (pinfunction "2_2") (pintype "passive"))
    )
    (net (code "71") (name "Net-(RO6B-Pad2)") (class "Default")
      (node (ref "RO6B") (pin "2") (pinfunction "2_2") (pintype "passive"))
      (node (ref "RO6C") (pin "2") (pinfunction "2_2") (pintype "passive"))
    )
    (net (code "72") (name "Net-(RO7B-Pad2)") (class "Default")
      (node (ref "RO7B") (pin "2") (pinfunction "2_2") (pintype "passive"))
      (node (ref "RO7C") (pin "2") (pinfunction "2_2") (pintype "passive"))
    )
    (net (code "73") (name "Net-(RO8B-Pad2)") (class "Default")
      (node (ref "RO8B") (pin "2") (pinfunction "2_2") (pintype "passive"))
      (node (ref "RO8C") (pin "2") (pinfunction "2_2") (pintype "passive"))
    )
    (net (code "74") (name "Net-(RO9B-Pad2)") (class "Default")
      (node (ref "RO9B") (pin "2") (pinfunction "2_2") (pintype "passive"))
      (node (ref "RO9C") (pin "2") (pinfunction "2_2") (pintype "passive"))
    )
    (net (code "75") (name "Net-(RO10B-Pad2)") (class "Default")
      (node (ref "RO10B") (pin "2") (pinfunction "2_2") (pintype "passive"))
      (node (ref "RO10C") (pin "2") (pinfunction "2_2") (pintype "passive"))
    )
    (net (code "76") (name "Net-(T1-B)") (class "Default")
      (node (ref "RO1A") (pin "1") (pinfunction "1_1") (pintype "passive"))
      (node (ref "T1") (pin "3") (pinfunction "B_3") (pintype "passive"))
    )
    (net (code "77") (name "Net-(T1-C)") (class "Default")
      (node (ref "455-1750-1-ND1") (pin "1") (pinfunction "1_1") (pintype "passive"))
      (node (ref "455-1750-1-ND10") (pin "1") (pinfunction "1_1") (pintype "passive"))
      (node (ref "455-1750-1-ND2") (pin "1") (pinfunction "1_1") (pintype "passive"))
      (node (ref "455-1750-1-ND3") (pin "1") (pinfunction "1_1") (pintype "passive"))
      (node (ref "455-1750-1-ND4") (pin "1") (pinfunction "1_1") (pintype "passive"))
      (node (ref "455-1750-1-ND5") (pin "1") (pinfunction "1_1") (pintype "passive"))
      (node (ref "455-1750-1-ND6") (pin "1") (pinfunction "1_1") (pintype "passive"))
      (node (ref "455-1750-1-ND7") (pin "1") (pinfunction "1_1") (pintype "passive"))
      (node (ref "455-1750-1-ND8") (pin "1") (pinfunction "1_1") (pintype "passive"))
      (node (ref "455-1750-1-ND9") (pin "1") (pinfunction "1_1") (pintype "passive"))
      (node (ref "RO10C") (pin "1") (pinfunction "1_1") (pintype "passive"))
      (node (ref "RO1C") (pin "1") (pinfunction "1_1") (pintype "passive"))
      (node (ref "RO2C") (pin "1") (pinfunction "1_1") (pintype "passive"))
      (node (ref "RO3C") (pin "1") (pinfunction "1_1") (pintype "passive"))
      (node (ref "RO4C") (pin "1") (pinfunction "1_1") (pintype "passive"))
      (node (ref "RO5C") (pin "1") (pinfunction "1_1") (pintype "passive"))
      (node (ref "RO6C") (pin "1") (pinfunction "1_1") (pintype "passive"))
      (node (ref "RO7C") (pin "1") (pinfunction "1_1") (pintype "passive"))
      (node (ref "RO8C") (pin "1") (pinfunction "1_1") (pintype "passive"))
      (node (ref "RO9C") (pin "1") (pinfunction "1_1") (pintype "passive"))
      (node (ref "T1") (pin "2") (pinfunction "C_2") (pintype "passive"))
      (node (ref "T10") (pin "2") (pinfunction "C_2") (pintype "passive"))
      (node (ref "T2") (pin "2") (pinfunction "C_2") (pintype "passive"))
      (node (ref "T3") (pin "2") (pinfunction "C_2") (pintype "passive"))
      (node (ref "T4") (pin "2") (pinfunction "C_2") (pintype "passive"))
      (node (ref "T5") (pin "2") (pinfunction "C_2") (pintype "passive"))
      (node (ref "T6") (pin "2") (pinfunction "C_2") (pintype "passive"))
      (node (ref "T7") (pin "2") (pinfunction "C_2") (pintype "passive"))
      (node (ref "T8") (pin "2") (pinfunction "C_2") (pintype "passive"))
      (node (ref "T9") (pin "2") (pinfunction "C_2") (pintype "passive"))
      (node (ref "VOLTAGE_REG") (pin "3") (pinfunction "OUT_3") (pintype "bidirectional"))
    )
    (net (code "78") (name "Net-(T2-B)") (class "Default")
      (node (ref "RO2A") (pin "1") (pinfunction "1_1") (pintype "passive"))
      (node (ref "T2") (pin "3") (pinfunction "B_3") (pintype "passive"))
    )
    (net (code "79") (name "Net-(T3-B)") (class "Default")
      (node (ref "RO3A") (pin "1") (pinfunction "1_1") (pintype "passive"))
      (node (ref "T3") (pin "3") (pinfunction "B_3") (pintype "passive"))
    )
    (net (code "80") (name "Net-(T4-B)") (class "Default")
      (node (ref "RO4A") (pin "1") (pinfunction "1_1") (pintype "passive"))
      (node (ref "T4") (pin "3") (pinfunction "B_3") (pintype "passive"))
    )
    (net (code "81") (name "Net-(T5-B)") (class "Default")
      (node (ref "RO5A") (pin "1") (pinfunction "1_1") (pintype "passive"))
      (node (ref "T5") (pin "3") (pinfunction "B_3") (pintype "passive"))
    )
    (net (code "82") (name "Net-(T6-B)") (class "Default")
      (node (ref "RO6A") (pin "1") (pinfunction "1_1") (pintype "passive"))
      (node (ref "T6") (pin "3") (pinfunction "B_3") (pintype "passive"))
    )
    (net (code "83") (name "Net-(T7-B)") (class "Default")
      (node (ref "RO7A") (pin "1") (pinfunction "1_1") (pintype "passive"))
      (node (ref "T7") (pin "3") (pinfunction "B_3") (pintype "passive"))
    )
    (net (code "84") (name "Net-(T8-B)") (class "Default")
      (node (ref "RO8A") (pin "1") (pinfunction "1_1") (pintype "passive"))
      (node (ref "T8") (pin "3") (pinfunction "B_3") (pintype "passive"))
    )
    (net (code "85") (name "Net-(T9-B)") (class "Default")
      (node (ref "RO9A") (pin "1") (pinfunction "1_1") (pintype "passive"))
      (node (ref "T9") (pin "3") (pinfunction "B_3") (pintype "passive"))
    )
    (net (code "86") (name "Net-(T10-B)") (class "Default")
      (node (ref "RO10A") (pin "1") (pinfunction "1_1") (pintype "passive"))
      (node (ref "T10") (pin "3") (pinfunction "B_3") (pintype "passive"))
    )
    (net (code "87") (name "Net-(U$1-Pad3.3V_4)") (class "Default")
      (node (ref "U$1") (pin "3.3V_4") (pinfunction "3.3V_4_3.3V_4") (pintype "bidirectional"))
      (node (ref "U$1") (pin "3.3V_5") (pinfunction "3.3V_5_3.3V_5") (pintype "bidirectional"))
      (node (ref "U$1") (pin "3.3V_6") (pinfunction "3.3V_6_3.3V_6") (pintype "bidirectional"))
    )
    (net (code "88") (name "Net-(VOLTAGE_REG-IN)") (class "Default")
      (node (ref "SWITCH1") (pin "2") (pinfunction "2_2") (pintype "passive"))
      (node (ref "VOLTAGE_REG") (pin "1") (pinfunction "IN_1") (pintype "bidirectional"))
    )
    (net (code "89") (name "unconnected-(455-1750-1-ND1-Pad2)") (class "Default")
      (node (ref "455-1750-1-ND1") (pin "2") (pinfunction "2_2") (pintype "passive"))
    )
    (net (code "90") (name "unconnected-(455-1750-1-ND2-Pad2)") (class "Default")
      (node (ref "455-1750-1-ND2") (pin "2") (pinfunction "2_2") (pintype "passive"))
    )
    (net (code "91") (name "unconnected-(455-1750-1-ND3-Pad2)") (class "Default")
      (node (ref "455-1750-1-ND3") (pin "2") (pinfunction "2_2") (pintype "passive"))
    )
    (net (code "92") (name "unconnected-(455-1750-1-ND4-Pad2)") (class "Default")
      (node (ref "455-1750-1-ND4") (pin "2") (pinfunction "2_2") (pintype "passive"))
    )
    (net (code "93") (name "unconnected-(455-1750-1-ND5-Pad2)") (class "Default")
      (node (ref "455-1750-1-ND5") (pin "2") (pinfunction "2_2") (pintype "passive"))
    )
    (net (code "94") (name "unconnected-(455-1750-1-ND6-Pad2)") (class "Default")
      (node (ref "455-1750-1-ND6") (pin "2") (pinfunction "2_2") (pintype "passive"))
    )
    (net (code "95") (name "unconnected-(455-1750-1-ND7-Pad2)") (class "Default")
      (node (ref "455-1750-1-ND7") (pin "2") (pinfunction "2_2") (pintype "passive"))
    )
    (net (code "96") (name "unconnected-(455-1750-1-ND8-Pad2)") (class "Default")
      (node (ref "455-1750-1-ND8") (pin "2") (pinfunction "2_2") (pintype "passive"))
    )
    (net (code "97") (name "unconnected-(455-1750-1-ND9-Pad2)") (class "Default")
      (node (ref "455-1750-1-ND9") (pin "2") (pinfunction "2_2") (pintype "passive"))
    )
    (net (code "98") (name "unconnected-(455-1750-1-ND10-Pad2)") (class "Default")
      (node (ref "455-1750-1-ND10") (pin "2") (pinfunction "2_2") (pintype "passive"))
    )
    (net (code "99") (name "unconnected-(CAN_TRANSCEIVER-RS-Pad8)") (class "Default")
      (node (ref "CAN_TRANSCEIVER") (pin "8") (pinfunction "RS_8") (pintype "input"))
    )
    (net (code "100") (name "unconnected-(IC1-BOOT0-Pad60)") (class "Default")
      (node (ref "IC1") (pin "60") (pinfunction "BOOT0_60") (pintype "passive"))
    )
    (net (code "101") (name "unconnected-(IC1-PA4-Pad20)") (class "Default")
      (node (ref "IC1") (pin "20") (pinfunction "PA4_20") (pintype "passive"))
    )
    (net (code "102") (name "unconnected-(IC1-PA5-Pad21)") (class "Default")
      (node (ref "IC1") (pin "21") (pinfunction "PA5_21") (pintype "passive"))
    )
    (net (code "103") (name "unconnected-(IC1-PA8-Pad41)") (class "Default")
      (node (ref "IC1") (pin "41") (pinfunction "PA8_41") (pintype "passive"))
    )
    (net (code "104") (name "unconnected-(IC1-PA9-Pad42)") (class "Default")
      (node (ref "IC1") (pin "42") (pinfunction "PA9_42") (pintype "passive"))
    )
    (net (code "105") (name "unconnected-(IC1-PA10-Pad43)") (class "Default")
      (node (ref "IC1") (pin "43") (pinfunction "PA10_43") (pintype "passive"))
    )
    (net (code "106") (name "unconnected-(IC1-PB2-Pad28)") (class "Default")
      (node (ref "IC1") (pin "28") (pinfunction "PB2_28") (pintype "passive"))
    )
    (net (code "107") (name "unconnected-(IC1-PB5-Pad57)") (class "Default")
      (node (ref "IC1") (pin "57") (pinfunction "PB5_57") (pintype "passive"))
    )
    (net (code "108") (name "unconnected-(IC1-PB6-Pad58)") (class "Default")
      (node (ref "IC1") (pin "58") (pinfunction "PB6_58") (pintype "passive"))
    )
    (net (code "109") (name "unconnected-(IC1-PB7-Pad59)") (class "Default")
      (node (ref "IC1") (pin "59") (pinfunction "PB7_59") (pintype "passive"))
    )
    (net (code "110") (name "unconnected-(IC1-PB12-Pad33)") (class "Default")
      (node (ref "IC1") (pin "33") (pinfunction "PB12_33") (pintype "passive"))
    )
    (net (code "111") (name "unconnected-(IC1-PB13-Pad34)") (class "Default")
      (node (ref "IC1") (pin "34") (pinfunction "PB13_34") (pintype "passive"))
    )
    (net (code "112") (name "unconnected-(IC1-PC4-Pad24)") (class "Default")
      (node (ref "IC1") (pin "24") (pinfunction "PC4_24") (pintype "passive"))
    )
    (net (code "113") (name "unconnected-(IC1-PC5-Pad25)") (class "Default")
      (node (ref "IC1") (pin "25") (pinfunction "PC5_25") (pintype "passive"))
    )
    (net (code "114") (name "unconnected-(IC1-PC9-Pad40)") (class "Default")
      (node (ref "IC1") (pin "40") (pinfunction "PC9_40") (pintype "passive"))
    )
    (net (code "115") (name "unconnected-(IC1-PC10-Pad51)") (class "Default")
      (node (ref "IC1") (pin "51") (pinfunction "PC10_51") (pintype "passive"))
    )
    (net (code "116") (name "unconnected-(IC1-PC11-Pad52)") (class "Default")
      (node (ref "IC1") (pin "52") (pinfunction "PC11_52") (pintype "passive"))
    )
    (net (code "117") (name "unconnected-(IC1-PC13-Pad2)") (class "Default")
      (node (ref "IC1") (pin "2") (pinfunction "PC13_2") (pintype "passive"))
    )
    (net (code "118") (name "unconnected-(IC1-PC14-Pad3)") (class "Default")
      (node (ref "IC1") (pin "3") (pinfunction "PC14_3") (pintype "passive"))
    )
    (net (code "119") (name "unconnected-(IC1-PC15-Pad4)") (class "Default")
      (node (ref "IC1") (pin "4") (pinfunction "PC15_4") (pintype "passive"))
    )
    (net (code "120") (name "unconnected-(IC1-VBAT-Pad1)") (class "Default")
      (node (ref "IC1") (pin "1") (pinfunction "VBAT_1") (pintype "passive"))
    )
    (net (code "121") (name "unconnected-(J1-PadID)") (class "Default")
      (node (ref "J1") (pin "ID") (pinfunction "ID_ID") (pintype "bidirectional"))
    )
    (net (code "122") (name "unconnected-(J4-Pad11)") (class "Default")
      (node (ref "J4") (pin "11") (pinfunction "11_11") (pintype "passive"))
    )
    (net (code "123") (name "unconnected-(J4-Pad17)") (class "Default")
      (node (ref "J4") (pin "17") (pinfunction "17_17") (pintype "passive"))
    )
    (net (code "124") (name "unconnected-(J4-Pad19)") (class "Default")
      (node (ref "J4") (pin "19") (pinfunction "19_19") (pintype "passive"))
    )
    (net (code "125") (name "unconnected-(J5-CMD(DI)-Pad3)") (class "Default")
      (node (ref "J5") (pin "3") (pinfunction "CMD(DI)_3") (pintype "bidirectional"))
    )
    (net (code "126") (name "unconnected-(J5-DAT1(RSV)-Pad8)") (class "Default")
      (node (ref "J5") (pin "8") (pinfunction "DAT1(RSV)_8") (pintype "bidirectional"))
    )
    (net (code "127") (name "unconnected-(J5-DAT2(NC)-Pad1)") (class "Default")
      (node (ref "J5") (pin "1") (pinfunction "DAT2(NC)_1") (pintype "bidirectional"))
    )
    (net (code "128") (name "unconnected-(J5-PadCD1)") (class "Default")
      (node (ref "J5") (pin "CD1") (pinfunction "CD1_CD1") (pintype "bidirectional"))
    )
    (net (code "129") (name "unconnected-(J5-PadCD2)") (class "Default")
      (node (ref "J5") (pin "CD2") (pinfunction "CD2_CD2") (pintype "bidirectional"))
    )
    (net (code "130") (name "unconnected-(RESET_SWITCH-0-Pad0A)") (class "Default")
      (node (ref "RESET_SWITCH") (pin "0A") (pinfunction "0_0A") (pintype "passive"))
    )
    (net (code "131") (name "unconnected-(U$1-PadEXTRA1)") (class "Default")
      (node (ref "U$1") (pin "EXTRA1") (pinfunction "EXTRA1_EXTRA1") (pintype "bidirectional"))
    )
    (net (code "132") (name "unconnected-(U$1-PadEXTRA2)") (class "Default")
      (node (ref "U$1") (pin "EXTRA2") (pinfunction "EXTRA2_EXTRA2") (pintype "bidirectional"))
    )
    (net (code "133") (name "unconnected-(U$1-PadEXTRA3)") (class "Default")
      (node (ref "U$1") (pin "EXTRA3") (pinfunction "EXTRA3_EXTRA3") (pintype "bidirectional"))
    )
    (net (code "134") (name "unconnected-(U$1-PadEXTRA4)") (class "Default")
      (node (ref "U$1") (pin "EXTRA4") (pinfunction "EXTRA4_EXTRA4") (pintype "bidirectional"))
    )
    (net (code "135") (name "unconnected-(U$1-PadEXTRA5)") (class "Default")
      (node (ref "U$1") (pin "EXTRA5") (pinfunction "EXTRA5_EXTRA5") (pintype "bidirectional"))
    )
    (net (code "136") (name "unconnected-(U$1-PadEXTRA6)") (class "Default")
      (node (ref "U$1") (pin "EXTRA6") (pinfunction "EXTRA6_EXTRA6") (pintype "bidirectional"))
    )
    (net (code "137") (name "unconnected-(U$1-PadEXTRA7)") (class "Default")
      (node (ref "U$1") (pin "EXTRA7") (pinfunction "EXTRA7_EXTRA7") (pintype "bidirectional"))
    )
    (net (code "138") (name "unconnected-(U$1-PadEXTRA8)") (class "Default")
      (node (ref "U$1") (pin "EXTRA8") (pinfunction "EXTRA8_EXTRA8") (pintype "bidirectional"))
    )
    (net (code "139") (name "unconnected-(U$1-PadEXTRA9)") (class "Default")
      (node (ref "U$1") (pin "EXTRA9") (pinfunction "EXTRA9_EXTRA9") (pintype "bidirectional"))
    )
    (net (code "140") (name "unconnected-(U$1-PadEXTRA10)") (class "Default")
      (node (ref "U$1") (pin "EXTRA10") (pinfunction "EXTRA10_EXTRA10") (pintype "bidirectional"))
    )
    (net (code "141") (name "unconnected-(U$1-PadEXTRA11)") (class "Default")
      (node (ref "U$1") (pin "EXTRA11") (pinfunction "EXTRA11_EXTRA11") (pintype "bidirectional"))
    )
    (net (code "142") (name "unconnected-(U$1-PadEXTRA12)") (class "Default")
      (node (ref "U$1") (pin "EXTRA12") (pinfunction "EXTRA12_EXTRA12") (pintype "bidirectional"))
    )
    (net (code "143") (name "unconnected-(U$1-PadEXTRA13)") (class "Default")
      (node (ref "U$1") (pin "EXTRA13") (pinfunction "EXTRA13_EXTRA13") (pintype "bidirectional"))
    )
    (net (code "144") (name "unconnected-(U$1-PadEXTRA14)") (class "Default")
      (node (ref "U$1") (pin "EXTRA14") (pinfunction "EXTRA14_EXTRA14") (pintype "bidirectional"))
    )
    (net (code "145") (name "unconnected-(U$1-PadEXTRA15)") (class "Default")
      (node (ref "U$1") (pin "EXTRA15") (pinfunction "EXTRA15_EXTRA15") (pintype "bidirectional"))
    )
    (net (code "146") (name "unconnected-(U$1-PadEXTRA16)") (class "Default")
      (node (ref "U$1") (pin "EXTRA16") (pinfunction "EXTRA16_EXTRA16") (pintype "bidirectional"))
    )
    (net (code "147") (name "unconnected-(U$1-PadEXTRA17)") (class "Default")
      (node (ref "U$1") (pin "EXTRA17") (pinfunction "EXTRA17_EXTRA17") (pintype "bidirectional"))
    )
    (net (code "148") (name "unconnected-(U$1-PadEXTRA18)") (class "Default")
      (node (ref "U$1") (pin "EXTRA18") (pinfunction "EXTRA18_EXTRA18") (pintype "bidirectional"))
    )
    (net (code "149") (name "unconnected-(U$1-PadEXTRA19)") (class "Default")
      (node (ref "U$1") (pin "EXTRA19") (pinfunction "EXTRA19_EXTRA19") (pintype "bidirectional"))
    )
    (net (code "150") (name "unconnected-(U$1-PadEXTRA20)") (class "Default")
      (node (ref "U$1") (pin "EXTRA20") (pinfunction "EXTRA20_EXTRA20") (pintype "bidirectional"))
    )
    (net (code "151") (name "unconnected-(U$1-PadEXTRA21)") (class "Default")
      (node (ref "U$1") (pin "EXTRA21") (pinfunction "EXTRA21_EXTRA21") (pintype "bidirectional"))
    )
    (net (code "152") (name "unconnected-(U$1-PadEXTRA22)") (class "Default")
      (node (ref "U$1") (pin "EXTRA22") (pinfunction "EXTRA22_EXTRA22") (pintype "bidirectional"))
    )
    (net (code "153") (name "unconnected-(U$1-PadEXTRA23)") (class "Default")
      (node (ref "U$1") (pin "EXTRA23") (pinfunction "EXTRA23_EXTRA23") (pintype "bidirectional"))
    )
    (net (code "154") (name "unconnected-(U$1-PadEXTRA24)") (class "Default")
      (node (ref "U$1") (pin "EXTRA24") (pinfunction "EXTRA24_EXTRA24") (pintype "bidirectional"))
    )
    (net (code "155") (name "unconnected-(U$1-PadEXTRA25)") (class "Default")
      (node (ref "U$1") (pin "EXTRA25") (pinfunction "EXTRA25_EXTRA25") (pintype "bidirectional"))
    )
    (net (code "156") (name "unconnected-(U$1-PadEXTRA26)") (class "Default")
      (node (ref "U$1") (pin "EXTRA26") (pinfunction "EXTRA26_EXTRA26") (pintype "bidirectional"))
    )
    (net (code "157") (name "unconnected-(U$1-PadEXTRA27)") (class "Default")
      (node (ref "U$1") (pin "EXTRA27") (pinfunction "EXTRA27_EXTRA27") (pintype "bidirectional"))
    )
    (net (code "158") (name "unconnected-(U$1-PadEXTRA28)") (class "Default")
      (node (ref "U$1") (pin "EXTRA28") (pinfunction "EXTRA28_EXTRA28") (pintype "bidirectional"))
    )
    (net (code "159") (name "unconnected-(U$1-PadEXTRA29)") (class "Default")
      (node (ref "U$1") (pin "EXTRA29") (pinfunction "EXTRA29_EXTRA29") (pintype "bidirectional"))
    )
    (net (code "160") (name "unconnected-(U$1-PadEXTRA30)") (class "Default")
      (node (ref "U$1") (pin "EXTRA30") (pinfunction "EXTRA30_EXTRA30") (pintype "bidirectional"))
    )
    (net (code "161") (name "unconnected-(U$1-PadEXTRA31)") (class "Default")
      (node (ref "U$1") (pin "EXTRA31") (pinfunction "EXTRA31_EXTRA31") (pintype "bidirectional"))
    )
    (net (code "162") (name "unconnected-(U$1-PadEXTRA32)") (class "Default")
      (node (ref "U$1") (pin "EXTRA32") (pinfunction "EXTRA32_EXTRA32") (pintype "bidirectional"))
    )
    (net (code "163") (name "unconnected-(U$1-PadEXTRA33)") (class "Default")
      (node (ref "U$1") (pin "EXTRA33") (pinfunction "EXTRA33_EXTRA33") (pintype "bidirectional"))
    )
    (net (code "164") (name "unconnected-(U$1-PadEXTRA34)") (class "Default")
      (node (ref "U$1") (pin "EXTRA34") (pinfunction "EXTRA34_EXTRA34") (pintype "bidirectional"))
    )
    (net (code "165") (name "unconnected-(U$1-PadEXTRA35)") (class "Default")
      (node (ref "U$1") (pin "EXTRA35") (pinfunction "EXTRA35_EXTRA35") (pintype "bidirectional"))
    )
    (net (code "166") (name "unconnected-(U$1-PadKILL_SWITCH)") (class "Default")
      (node (ref "U$1") (pin "KILL_SWITCH") (pinfunction "KILL_SWITCH_KILL_SWITCH") (pintype "bidirectional"))
    )
    (net (code "167") (name "unconnected-(U$1-PadSCL_DEPTH)") (class "Default")
      (node (ref "U$1") (pin "SCL_DEPTH") (pinfunction "SCL_DEPTH_SCL_DEPTH") (pintype "bidirectional"))
    )
    (net (code "168") (name "unconnected-(U$1-PadSCL_ESC)") (class "Default")
      (node (ref "U$1") (pin "SCL_ESC") (pinfunction "SCL_ESC_SCL_ESC") (pintype "bidirectional"))
    )
    (net (code "169") (name "unconnected-(U$1-PadSCL_SENSOR)") (class "Default")
      (node (ref "U$1") (pin "SCL_SENSOR") (pinfunction "SCL_SENSOR_SCL_SENSOR") (pintype "bidirectional"))
    )
    (net (code "170") (name "unconnected-(U$1-PadSDA_DEPTH)") (class "Default")
      (node (ref "U$1") (pin "SDA_DEPTH") (pinfunction "SDA_DEPTH_SDA_DEPTH") (pintype "bidirectional"))
    )
    (net (code "171") (name "unconnected-(U$1-PadSDA_ESC)") (class "Default")
      (node (ref "U$1") (pin "SDA_ESC") (pinfunction "SDA_ESC_SDA_ESC") (pintype "bidirectional"))
    )
    (net (code "172") (name "unconnected-(U$1-PadSDA_SENSOR)") (class "Default")
      (node (ref "U$1") (pin "SDA_SENSOR") (pinfunction "SDA_SENSOR_SDA_SENSOR") (pintype "bidirectional"))
    )
    (net (code "173") (name "unconnected-(VOLTAGE_REG-GND2-PadPAD)") (class "Default")
      (node (ref "VOLTAGE_REG") (pin "PAD") (pinfunction "GND2_PAD") (pintype "bidirectional"))
    )
  )
)
